# Sheet1.net
KiCad netlist of a schematic drawn in Altium Designer
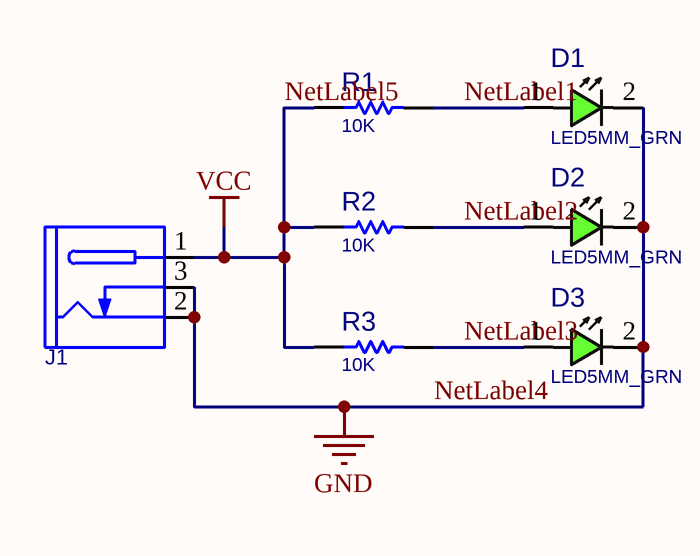
[diagram p0: Sheet1.SchDoc]

(export (version "E")
  (design (tool "Eeschema 10.0.6"))
  (components
    (comp (ref "D1")
      (value "LED5MM_GRN")
      (footprint "LED5MM_GRN")
      (description "LED, THD, 5MM, GREEN")
      (fields (field (name "MANF") "MANF") (field (name "MANF_P#") "MANF_PART#"))
      (libsource (lib "led(diode)") (part "LED_THD_5MM_GRN"))
    )
    (comp (ref "D2")
      (value "LED5MM_GRN")
      (footprint "LED5MM_GRN")
      (description "LED, THD, 5MM, GREEN")
      (fields (field (name "MANF") "MANF") (field (name "MANF_P#") "MANF_PART#"))
      (libsource (lib "led(diode)") (part "LED_THD_5MM_GRN"))
    )
    (comp (ref "D3")
      (value "LED5MM_GRN")
      (footprint "LED5MM_GRN")
      (description "LED, THD, 5MM, GREEN")
      (fields (field (name "MANF") "MANF") (field (name "MANF_P#") "MANF_PART#"))
      (libsource (lib "led(diode)") (part "LED_THD_5MM_GRN"))
    )
    (comp (ref "J1")
      (value "DC_POWER_JACK")
      (footprint "JAC_PWR1")
      (description "CONN, PWR JACK DC, PLUG DIAM 1.0MM RA THD")
      (fields (field (name "MANF") "CUI STACK") (field (name "MANF_P#") "PJ-031CH, PJ-031C"))
      (libsource (lib "conn_powerJack") (part "CONN_PWR_JACKR1"))
    )
    (comp (ref "R1")
      (value "10K")
      (footprint "R025W_AX04")
      (description "RESISTOR, THD")
      (fields (field (name "MANF_P#") "RK73H1ETTP4701F") (field (name "MANF") "KOA SPEER"))
      (libsource (lib "passive_thd") (part "RES_THD"))
    )
    (comp (ref "R2")
      (value "10K")
      (footprint "R025W_AX04")
      (description "RESISTOR, THD")
      (fields (field (name "MANF_P#") "RK73H1ETTP4701F") (field (name "MANF") "KOA SPEER"))
      (libsource (lib "passive_thd") (part "RES_THD"))
    )
    (comp (ref "R3")
      (value "10K")
      (footprint "R025W_AX04")
      (description "RESISTOR, THD")
      (fields (field (name "MANF_P#") "RK73H1ETTP4701F") (field (name "MANF") "KOA SPEER"))
      (libsource (lib "passive_thd") (part "RES_THD"))
    )
  )
  (nets
    (net (code "1") (name "/NetLabel1") (class "Default")
      (node (ref "D1") (pin "1") (pinfunction "ANODE_1") (pintype "passive"))
      (node (ref "R1") (pin "2") (pinfunction "2_2") (pintype "passive"))
    )
    (net (code "2") (name "/NetLabel2") (class "Default")
      (node (ref "D2") (pin "1") (pinfunction "ANODE_1") (pintype "passive"))
      (node (ref "R2") (pin "2") (pinfunction "2_2") (pintype "passive"))
    )
    (net (code "3") (name "/NetLabel3") (class "Default")
      (node (ref "D3") (pin "1") (pinfunction "ANODE_1") (pintype "passive"))
      (node (ref "R3") (pin "2") (pinfunction "2_2") (pintype "passive"))
    )
    (net (code "4") (name "GND") (class "Default")
      (node (ref "D1") (pin "2") (pinfunction "CATHODE_2") (pintype "passive"))
      (node (ref "D2") (pin "2") (pinfunction "CATHODE_2") (pintype "passive"))
      (node (ref "D3") (pin "2") (pinfunction "CATHODE_2") (pintype "passive"))
      (node (ref "J1") (pin "2") (pinfunction "SLEEVE_2") (pintype "power_in"))
      (node (ref "J1") (pin "3") (pinfunction "INSERTION_DET_3") (pintype "power_in"))
    )
    (net (code "5") (name "VCC") (class "Default")
      (node (ref "J1") (pin "1") (pinfunction "TIP_1") (pintype "power_in"))
      (node (ref "R1") (pin "1") (pinfunction "1_1") (pintype "passive"))
      (node (ref "R2") (pin "1") (pinfunction "1_1") (pintype "passive"))
      (node (ref "R3") (pin "1") (pinfunction "1_1") (pintype "passive"))
    )
  )
)
